# S7CAS-PLEIADES-CARTE-MERE_P01_FPGA-ALIM.net
KiCad netlist of a schematic drawn in Altium Designer
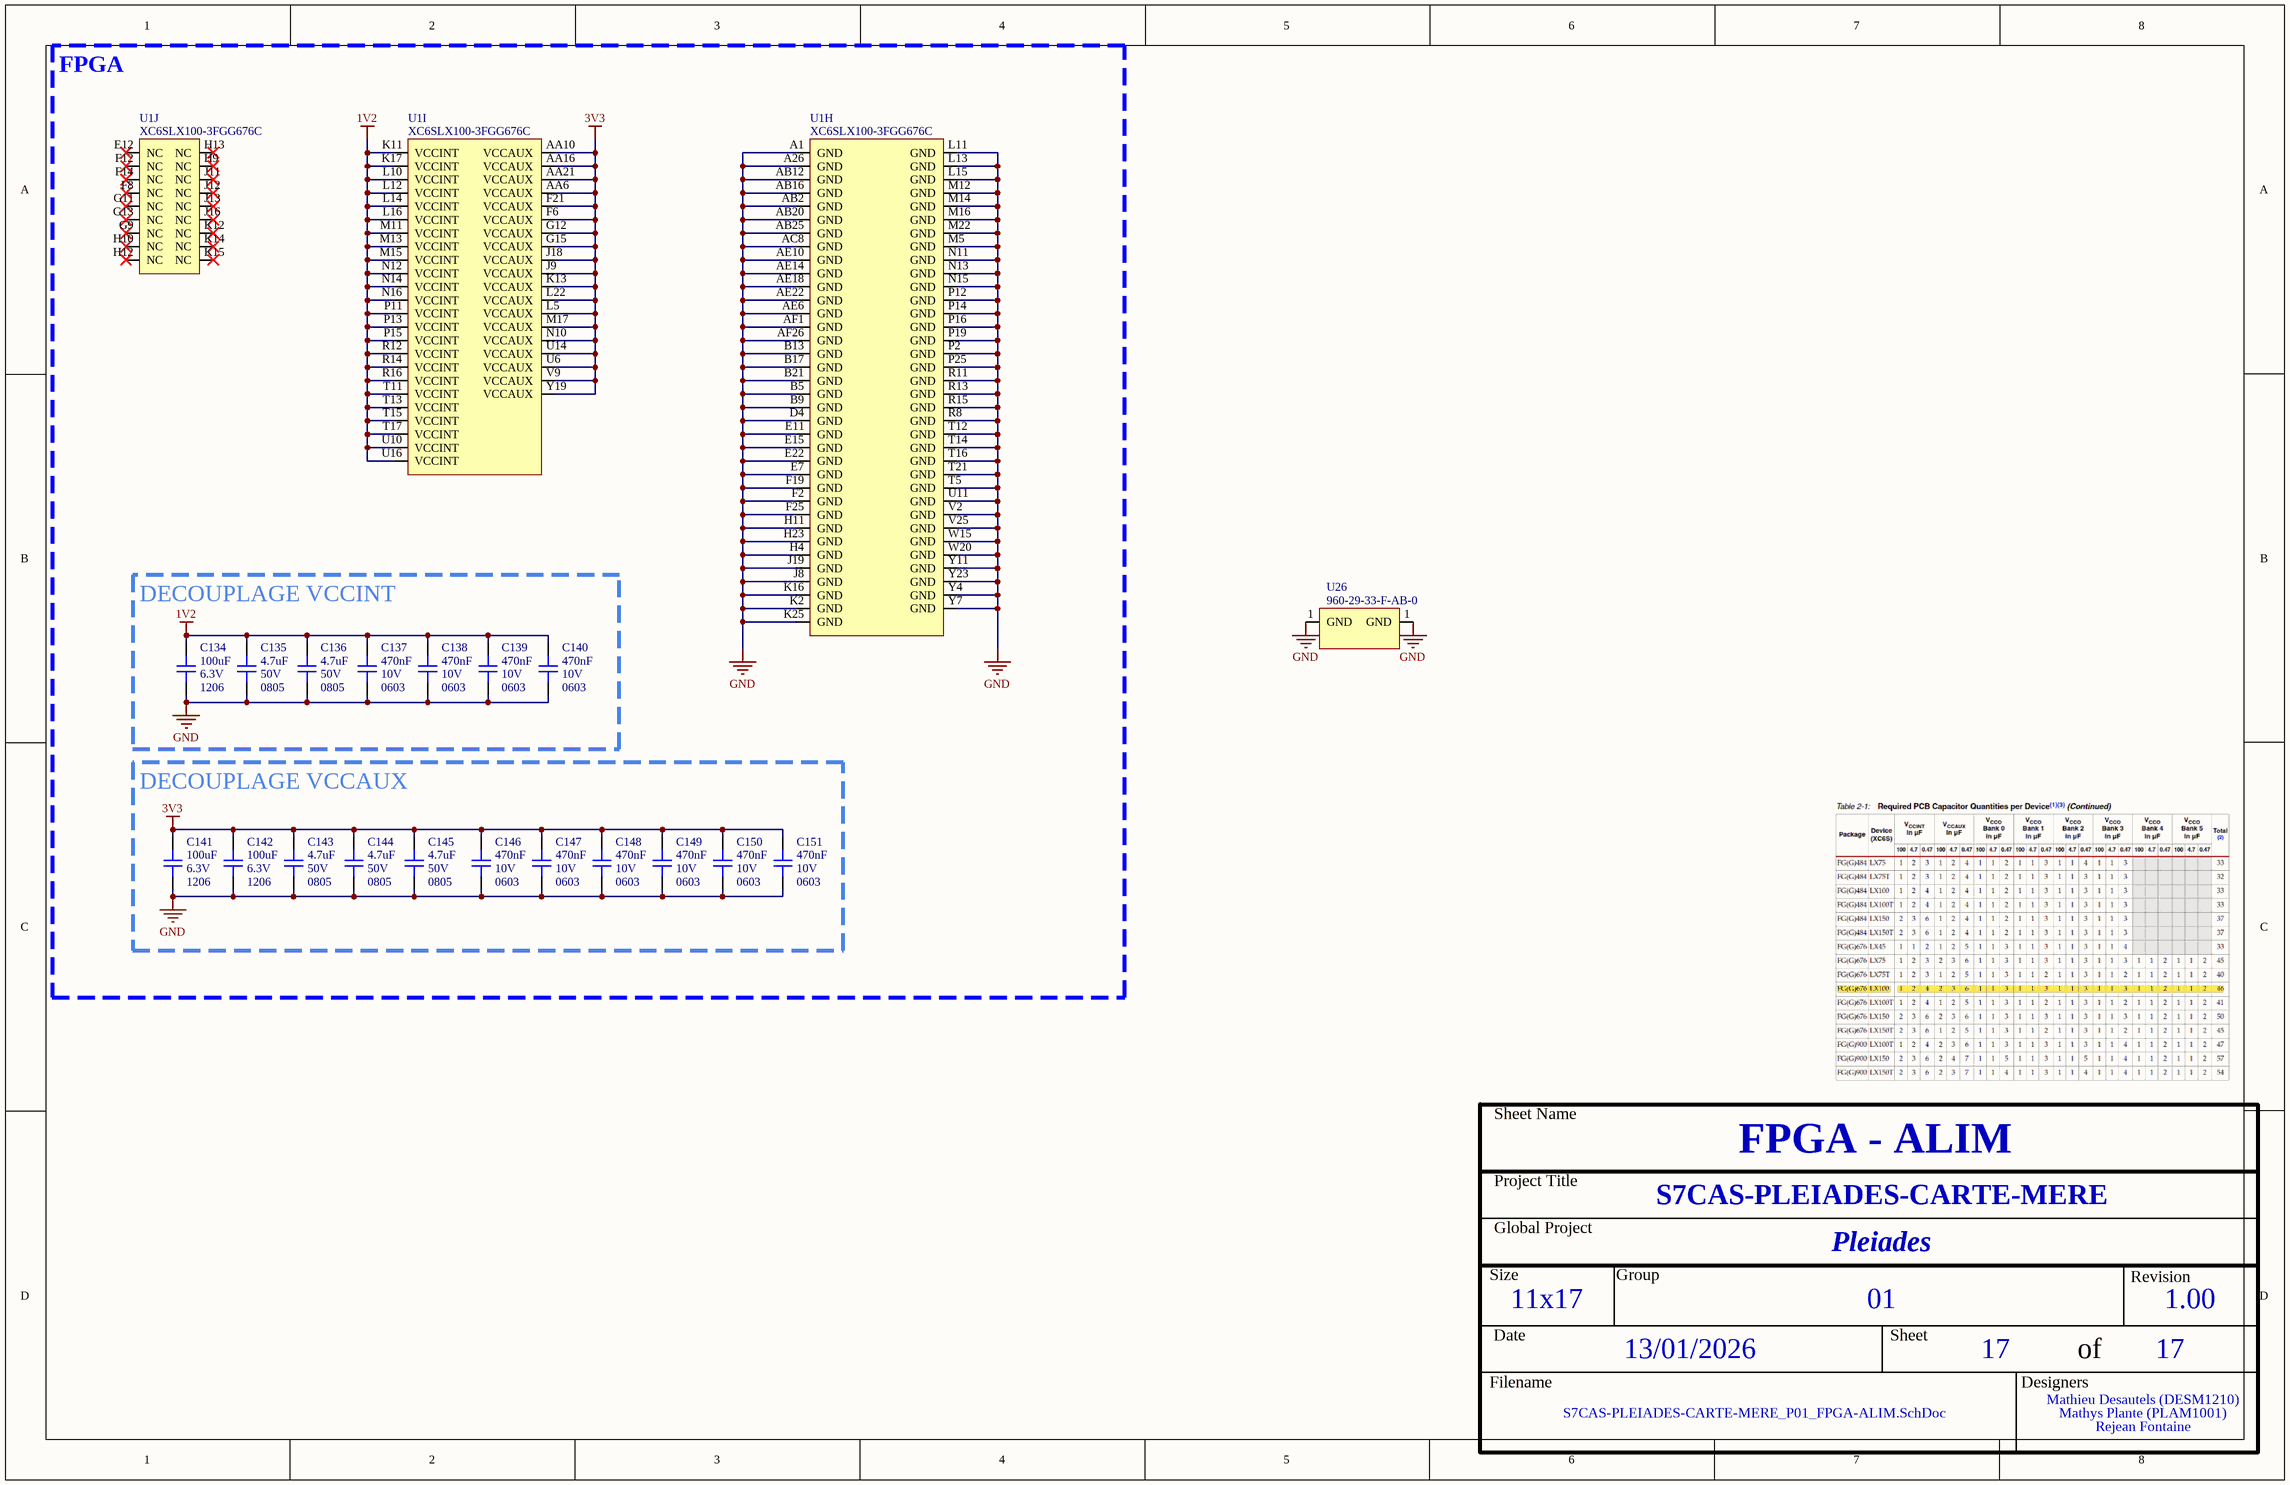
[diagram p0: S7CAS-PLEIADES-CARTE-MERE_P01_FPGA-ALIM.SchDoc]

(export (version "E")
  (design (tool "Eeschema 10.0.6"))
  (components
    (comp (ref "C134")
      (value "100uF")
      (footprint "CAP_1206")
      (description "100 µF ±20% 6.3V Ceramic Capacitor X6T 1206 (3216 Metric)")
      (fields
        (field (name "MFG") "Murata Electronics")
        (field (name "MFG PART NUMBER") "GRM31CD80J107MEA8K")
        (field (name "VOLTAGE") "6.3V")
        (field (name "PACKAGE") "1206")
        (field (name "CREATEDBY") "Jonathan Bouchard")
      )
      (libsource (lib "s7cas_lib2023") (part "CAP - 1206"))
    )
    (comp (ref "C135")
      (value "4.7uF")
      (footprint "CAP_0805")
      (description "4.7 µF ±10% 50V Ceramic Capacitor X5R 0805 (2012 Metric)")
      (fields
        (field (name "MFG") "Murata Electronics")
        (field (name "MFG PART NUMBER") "GRT21BR61H475KE13L")
        (field (name "VOLTAGE") "50V")
        (field (name "PACKAGE") "0805")
        (field (name "CREATEDBY") "Jonathan Bouchard")
      )
      (libsource (lib "s7cas_lib2023") (part "CAP - 0805"))
    )
    (comp (ref "C136")
      (value "4.7uF")
      (footprint "CAP_0805")
      (description "4.7 µF ±10% 50V Ceramic Capacitor X5R 0805 (2012 Metric)")
      (fields
        (field (name "MFG") "Murata Electronics")
        (field (name "MFG PART NUMBER") "GRT21BR61H475KE13L")
        (field (name "VOLTAGE") "50V")
        (field (name "PACKAGE") "0805")
        (field (name "CREATEDBY") "Jonathan Bouchard")
      )
      (libsource (lib "s7cas_lib2023") (part "CAP - 0805"))
    )
    (comp (ref "C137")
      (value "470nF")
      (footprint "CAP_0603")
      (description "CAP - 0603")
      (fields
        (field (name "MFG PART NUMBER") "C0603X474K8RAC")
        (field (name "VOLTAGE") "10V")
        (field (name "PACKAGE") "0603")
        (field (name "CREATEDBY") "Jonathan Bouchard")
      )
      (libsource (lib "s7cas_lib2023") (part "CAP - 0603"))
    )
    (comp (ref "C138")
      (value "470nF")
      (footprint "CAP_0603")
      (description "CAP - 0603")
      (fields
        (field (name "MFG PART NUMBER") "C0603X474K8RAC")
        (field (name "VOLTAGE") "10V")
        (field (name "PACKAGE") "0603")
        (field (name "CREATEDBY") "Jonathan Bouchard")
      )
      (libsource (lib "s7cas_lib2023") (part "CAP - 0603"))
    )
    (comp (ref "C139")
      (value "470nF")
      (footprint "CAP_0603")
      (description "CAP - 0603")
      (fields
        (field (name "MFG PART NUMBER") "C0603X474K8RAC")
        (field (name "VOLTAGE") "10V")
        (field (name "PACKAGE") "0603")
        (field (name "CREATEDBY") "Jonathan Bouchard")
      )
      (libsource (lib "s7cas_lib2023") (part "CAP - 0603"))
    )
    (comp (ref "C140")
      (value "470nF")
      (footprint "CAP_0603")
      (description "CAP - 0603")
      (fields
        (field (name "MFG PART NUMBER") "C0603X474K8RAC")
        (field (name "VOLTAGE") "10V")
        (field (name "PACKAGE") "0603")
        (field (name "CREATEDBY") "Jonathan Bouchard")
      )
      (libsource (lib "s7cas_lib2023") (part "CAP - 0603"))
    )
    (comp (ref "C141")
      (value "100uF")
      (footprint "CAP_1206")
      (description "100 µF ±20% 6.3V Ceramic Capacitor X6T 1206 (3216 Metric)")
      (fields
        (field (name "MFG") "Murata Electronics")
        (field (name "MFG PART NUMBER") "GRM31CD80J107MEA8K")
        (field (name "VOLTAGE") "6.3V")
        (field (name "PACKAGE") "1206")
        (field (name "CREATEDBY") "Jonathan Bouchard")
      )
      (libsource (lib "s7cas_lib2023") (part "CAP - 1206"))
    )
    (comp (ref "C142")
      (value "100uF")
      (footprint "CAP_1206")
      (description "100 µF ±20% 6.3V Ceramic Capacitor X6T 1206 (3216 Metric)")
      (fields
        (field (name "MFG") "Murata Electronics")
        (field (name "MFG PART NUMBER") "GRM31CD80J107MEA8K")
        (field (name "VOLTAGE") "6.3V")
        (field (name "PACKAGE") "1206")
        (field (name "CREATEDBY") "Jonathan Bouchard")
      )
      (libsource (lib "s7cas_lib2023") (part "CAP - 1206"))
    )
    (comp (ref "C143")
      (value "4.7uF")
      (footprint "CAP_0805")
      (description "4.7 µF ±10% 50V Ceramic Capacitor X5R 0805 (2012 Metric)")
      (fields
        (field (name "MFG") "Murata Electronics")
        (field (name "MFG PART NUMBER") "GRT21BR61H475KE13L")
        (field (name "VOLTAGE") "50V")
        (field (name "PACKAGE") "0805")
        (field (name "CREATEDBY") "Jonathan Bouchard")
      )
      (libsource (lib "s7cas_lib2023") (part "CAP - 0805"))
    )
    (comp (ref "C144")
      (value "4.7uF")
      (footprint "CAP_0805")
      (description "4.7 µF ±10% 50V Ceramic Capacitor X5R 0805 (2012 Metric)")
      (fields
        (field (name "MFG") "Murata Electronics")
        (field (name "MFG PART NUMBER") "GRT21BR61H475KE13L")
        (field (name "VOLTAGE") "50V")
        (field (name "PACKAGE") "0805")
        (field (name "CREATEDBY") "Jonathan Bouchard")
      )
      (libsource (lib "s7cas_lib2023") (part "CAP - 0805"))
    )
    (comp (ref "C145")
      (value "4.7uF")
      (footprint "CAP_0805")
      (description "4.7 µF ±10% 50V Ceramic Capacitor X5R 0805 (2012 Metric)")
      (fields
        (field (name "MFG") "Murata Electronics")
        (field (name "MFG PART NUMBER") "GRT21BR61H475KE13L")
        (field (name "VOLTAGE") "50V")
        (field (name "PACKAGE") "0805")
        (field (name "CREATEDBY") "Jonathan Bouchard")
      )
      (libsource (lib "s7cas_lib2023") (part "CAP - 0805"))
    )
    (comp (ref "C146")
      (value "470nF")
      (footprint "CAP_0603")
      (description "CAP - 0603")
      (fields
        (field (name "MFG PART NUMBER") "C0603X474K8RAC")
        (field (name "VOLTAGE") "10V")
        (field (name "PACKAGE") "0603")
        (field (name "CREATEDBY") "Jonathan Bouchard")
      )
      (libsource (lib "s7cas_lib2023") (part "CAP - 0603"))
    )
    (comp (ref "C147")
      (value "470nF")
      (footprint "CAP_0603")
      (description "CAP - 0603")
      (fields
        (field (name "MFG PART NUMBER") "C0603X474K8RAC")
        (field (name "VOLTAGE") "10V")
        (field (name "PACKAGE") "0603")
        (field (name "CREATEDBY") "Jonathan Bouchard")
      )
      (libsource (lib "s7cas_lib2023") (part "CAP - 0603"))
    )
    (comp (ref "C148")
      (value "470nF")
      (footprint "CAP_0603")
      (description "CAP - 0603")
      (fields
        (field (name "MFG PART NUMBER") "C0603X474K8RAC")
        (field (name "VOLTAGE") "10V")
        (field (name "PACKAGE") "0603")
        (field (name "CREATEDBY") "Jonathan Bouchard")
      )
      (libsource (lib "s7cas_lib2023") (part "CAP - 0603"))
    )
    (comp (ref "C149")
      (value "470nF")
      (footprint "CAP_0603")
      (description "CAP - 0603")
      (fields
        (field (name "MFG PART NUMBER") "C0603X474K8RAC")
        (field (name "VOLTAGE") "10V")
        (field (name "PACKAGE") "0603")
        (field (name "CREATEDBY") "Jonathan Bouchard")
      )
      (libsource (lib "s7cas_lib2023") (part "CAP - 0603"))
    )
    (comp (ref "C150")
      (value "470nF")
      (footprint "CAP_0603")
      (description "CAP - 0603")
      (fields
        (field (name "MFG PART NUMBER") "C0603X474K8RAC")
        (field (name "VOLTAGE") "10V")
        (field (name "PACKAGE") "0603")
        (field (name "CREATEDBY") "Jonathan Bouchard")
      )
      (libsource (lib "s7cas_lib2023") (part "CAP - 0603"))
    )
    (comp (ref "C151")
      (value "470nF")
      (footprint "CAP_0603")
      (description "CAP - 0603")
      (fields
        (field (name "MFG PART NUMBER") "C0603X474K8RAC")
        (field (name "VOLTAGE") "10V")
        (field (name "PACKAGE") "0603")
        (field (name "CREATEDBY") "Jonathan Bouchard")
      )
      (libsource (lib "s7cas_lib2023") (part "CAP - 0603"))
    )
    (comp (ref "U1")
      (value "XC6SLX100-3FGG676C")
      (footprint "FPGA_XILINX_FGG676")
      (description "FPGA - XILINX SPARTAN 6 480 I/O - BGA-676")
      (fields
        (field (name "VOLTAGE") "1.14 V ~ 1.26 V")
        (field (name "MFG") "Xilinx")
        (field (name "CREATEDBY") "Jonathan Bouchard")
      )
      (libsource (lib "s7cas_lib2023") (part "FPGA_XC6SLX100-3FGG676C"))
    )
    (comp (ref "U26")
      (value "960-29-33-F-AB-0")
      (footprint "3960-29-33-F-AB-0")
      (description "XXX - Description - Package")
      (libsource (lib "HeatSink_SCH") (part "960-29-33-F-AB-0"))
    )
  )
  (nets
    (net (code "1") (name "1V2") (class "Default")
      (node (ref "C134") (pin "2") (pinfunction "2_2") (pintype "passive"))
      (node (ref "C135") (pin "2") (pinfunction "2_2") (pintype "passive"))
      (node (ref "C136") (pin "2") (pinfunction "2_2") (pintype "passive"))
      (node (ref "C137") (pin "2") (pinfunction "2_2") (pintype "passive"))
      (node (ref "C138") (pin "2") (pinfunction "2_2") (pintype "passive"))
      (node (ref "C139") (pin "2") (pinfunction "2_2") (pintype "passive"))
      (node (ref "C140") (pin "2") (pinfunction "2_2") (pintype "passive"))
      (node (ref "U1") (pin "K11") (pinfunction "VCCINT_K11") (pintype "passive"))
      (node (ref "U1") (pin "K17") (pinfunction "VCCINT_K17") (pintype "passive"))
      (node (ref "U1") (pin "L10") (pinfunction "VCCINT_L10") (pintype "passive"))
      (node (ref "U1") (pin "L12") (pinfunction "VCCINT_L12") (pintype "passive"))
      (node (ref "U1") (pin "L14") (pinfunction "VCCINT_L14") (pintype "passive"))
      (node (ref "U1") (pin "L16") (pinfunction "VCCINT_L16") (pintype "passive"))
      (node (ref "U1") (pin "M11") (pinfunction "VCCINT_M11") (pintype "passive"))
      (node (ref "U1") (pin "M13") (pinfunction "VCCINT_M13") (pintype "passive"))
      (node (ref "U1") (pin "M15") (pinfunction "VCCINT_M15") (pintype "passive"))
      (node (ref "U1") (pin "N12") (pinfunction "VCCINT_N12") (pintype "passive"))
      (node (ref "U1") (pin "N14") (pinfunction "VCCINT_N14") (pintype "passive"))
      (node (ref "U1") (pin "N16") (pinfunction "VCCINT_N16") (pintype "passive"))
      (node (ref "U1") (pin "P11") (pinfunction "VCCINT_P11") (pintype "passive"))
      (node (ref "U1") (pin "P13") (pinfunction "VCCINT_P13") (pintype "passive"))
      (node (ref "U1") (pin "P15") (pinfunction "VCCINT_P15") (pintype "passive"))
      (node (ref "U1") (pin "R12") (pinfunction "VCCINT_R12") (pintype "passive"))
      (node (ref "U1") (pin "R14") (pinfunction "VCCINT_R14") (pintype "passive"))
      (node (ref "U1") (pin "R16") (pinfunction "VCCINT_R16") (pintype "passive"))
      (node (ref "U1") (pin "T11") (pinfunction "VCCINT_T11") (pintype "passive"))
      (node (ref "U1") (pin "T13") (pinfunction "VCCINT_T13") (pintype "passive"))
      (node (ref "U1") (pin "T15") (pinfunction "VCCINT_T15") (pintype "passive"))
      (node (ref "U1") (pin "T17") (pinfunction "VCCINT_T17") (pintype "passive"))
      (node (ref "U1") (pin "U10") (pinfunction "VCCINT_U10") (pintype "passive"))
      (node (ref "U1") (pin "U16") (pinfunction "VCCINT_U16") (pintype "passive"))
    )
    (net (code "2") (name "3V3") (class "Default")
      (node (ref "C141") (pin "2") (pinfunction "2_2") (pintype "passive"))
      (node (ref "C142") (pin "2") (pinfunction "2_2") (pintype "passive"))
      (node (ref "C143") (pin "2") (pinfunction "2_2") (pintype "passive"))
      (node (ref "C144") (pin "2") (pinfunction "2_2") (pintype "passive"))
      (node (ref "C145") (pin "2") (pinfunction "2_2") (pintype "passive"))
      (node (ref "C146") (pin "2") (pinfunction "2_2") (pintype "passive"))
      (node (ref "C147") (pin "2") (pinfunction "2_2") (pintype "passive"))
      (node (ref "C148") (pin "2") (pinfunction "2_2") (pintype "passive"))
      (node (ref "C149") (pin "2") (pinfunction "2_2") (pintype "passive"))
      (node (ref "C150") (pin "2") (pinfunction "2_2") (pintype "passive"))
      (node (ref "C151") (pin "2") (pinfunction "2_2") (pintype "passive"))
      (node (ref "U1") (pin "AA10") (pinfunction "VCCAUX_AA10") (pintype "passive"))
      (node (ref "U1") (pin "AA16") (pinfunction "VCCAUX_AA16") (pintype "passive"))
      (node (ref "U1") (pin "AA21") (pinfunction "VCCAUX_AA21") (pintype "passive"))
      (node (ref "U1") (pin "AA6") (pinfunction "VCCAUX_AA6") (pintype "passive"))
      (node (ref "U1") (pin "F21") (pinfunction "VCCAUX_F21") (pintype "passive"))
      (node (ref "U1") (pin "F6") (pinfunction "VCCAUX_F6") (pintype "passive"))
      (node (ref "U1") (pin "G12") (pinfunction "VCCAUX_G12") (pintype "passive"))
      (node (ref "U1") (pin "G15") (pinfunction "VCCAUX_G15") (pintype "passive"))
      (node (ref "U1") (pin "J18") (pinfunction "VCCAUX_J18") (pintype "passive"))
      (node (ref "U1") (pin "J9") (pinfunction "VCCAUX_J9") (pintype "passive"))
      (node (ref "U1") (pin "K13") (pinfunction "VCCAUX_K13") (pintype "passive"))
      (node (ref "U1") (pin "L22") (pinfunction "VCCAUX_L22") (pintype "passive"))
      (node (ref "U1") (pin "L5") (pinfunction "VCCAUX_L5") (pintype "passive"))
      (node (ref "U1") (pin "M17") (pinfunction "VCCAUX_M17") (pintype "passive"))
      (node (ref "U1") (pin "N10") (pinfunction "VCCAUX_N10") (pintype "passive"))
      (node (ref "U1") (pin "U14") (pinfunction "VCCAUX_U14") (pintype "passive"))
      (node (ref "U1") (pin "U6") (pinfunction "VCCAUX_U6") (pintype "passive"))
      (node (ref "U1") (pin "V9") (pinfunction "VCCAUX_V9") (pintype "passive"))
      (node (ref "U1") (pin "Y19") (pinfunction "VCCAUX_Y19") (pintype "passive"))
    )
    (net (code "3") (name "GND") (class "Default")
      (node (ref "C134") (pin "1") (pinfunction "1_1") (pintype "passive"))
      (node (ref "C135") (pin "1") (pinfunction "1_1") (pintype "passive"))
      (node (ref "C136") (pin "1") (pinfunction "1_1") (pintype "passive"))
      (node (ref "C137") (pin "1") (pinfunction "1_1") (pintype "passive"))
      (node (ref "C138") (pin "1") (pinfunction "1_1") (pintype "passive"))
      (node (ref "C139") (pin "1") (pinfunction "1_1") (pintype "passive"))
      (node (ref "C140") (pin "1") (pinfunction "1_1") (pintype "passive"))
      (node (ref "C141") (pin "1") (pinfunction "1_1") (pintype "passive"))
      (node (ref "C142") (pin "1") (pinfunction "1_1") (pintype "passive"))
      (node (ref "C143") (pin "1") (pinfunction "1_1") (pintype "passive"))
      (node (ref "C144") (pin "1") (pinfunction "1_1") (pintype "passive"))
      (node (ref "C145") (pin "1") (pinfunction "1_1") (pintype "passive"))
      (node (ref "C146") (pin "1") (pinfunction "1_1") (pintype "passive"))
      (node (ref "C147") (pin "1") (pinfunction "1_1") (pintype "passive"))
      (node (ref "C148") (pin "1") (pinfunction "1_1") (pintype "passive"))
      (node (ref "C149") (pin "1") (pinfunction "1_1") (pintype "passive"))
      (node (ref "C150") (pin "1") (pinfunction "1_1") (pintype "passive"))
      (node (ref "C151") (pin "1") (pinfunction "1_1") (pintype "passive"))
      (node (ref "U1") (pin "A1") (pinfunction "GND_A1") (pintype "passive"))
      (node (ref "U1") (pin "A26") (pinfunction "GND_A26") (pintype "passive"))
      (node (ref "U1") (pin "AB12") (pinfunction "GND_AB12") (pintype "passive"))
      (node (ref "U1") (pin "AB16") (pinfunction "GND_AB16") (pintype "passive"))
      (node (ref "U1") (pin "AB2") (pinfunction "GND_AB2") (pintype "passive"))
      (node (ref "U1") (pin "AB20") (pinfunction "GND_AB20") (pintype "passive"))
      (node (ref "U1") (pin "AB25") (pinfunction "GND_AB25") (pintype "passive"))
      (node (ref "U1") (pin "AC8") (pinfunction "GND_AC8") (pintype "passive"))
      (node (ref "U1") (pin "AE10") (pinfunction "GND_AE10") (pintype "passive"))
      (node (ref "U1") (pin "AE14") (pinfunction "GND_AE14") (pintype "passive"))
      (node (ref "U1") (pin "AE18") (pinfunction "GND_AE18") (pintype "passive"))
      (node (ref "U1") (pin "AE22") (pinfunction "GND_AE22") (pintype "passive"))
      (node (ref "U1") (pin "AE6") (pinfunction "GND_AE6") (pintype "passive"))
      (node (ref "U1") (pin "AF1") (pinfunction "GND_AF1") (pintype "passive"))
      (node (ref "U1") (pin "AF26") (pinfunction "GND_AF26") (pintype "passive"))
      (node (ref "U1") (pin "B13") (pinfunction "GND_B13") (pintype "passive"))
      (node (ref "U1") (pin "B17") (pinfunction "GND_B17") (pintype "passive"))
      (node (ref "U1") (pin "B21") (pinfunction "GND_B21") (pintype "passive"))
      (node (ref "U1") (pin "B5") (pinfunction "GND_B5") (pintype "passive"))
      (node (ref "U1") (pin "B9") (pinfunction "GND_B9") (pintype "passive"))
      (node (ref "U1") (pin "D4") (pinfunction "GND_D4") (pintype "passive"))
      (node (ref "U1") (pin "E11") (pinfunction "GND_E11") (pintype "passive"))
      (node (ref "U1") (pin "E15") (pinfunction "GND_E15") (pintype "passive"))
      (node (ref "U1") (pin "E22") (pinfunction "GND_E22") (pintype "passive"))
      (node (ref "U1") (pin "E7") (pinfunction "GND_E7") (pintype "passive"))
      (node (ref "U1") (pin "F19") (pinfunction "GND_F19") (pintype "passive"))
      (node (ref "U1") (pin "F2") (pinfunction "GND_F2") (pintype "passive"))
      (node (ref "U1") (pin "F25") (pinfunction "GND_F25") (pintype "passive"))
      (node (ref "U1") (pin "H11") (pinfunction "GND_H11") (pintype "passive"))
      (node (ref "U1") (pin "H23") (pinfunction "GND_H23") (pintype "passive"))
      (node (ref "U1") (pin "H4") (pinfunction "GND_H4") (pintype "passive"))
      (node (ref "U1") (pin "J19") (pinfunction "GND_J19") (pintype "passive"))
      (node (ref "U1") (pin "J8") (pinfunction "GND_J8") (pintype "passive"))
      (node (ref "U1") (pin "K16") (pinfunction "GND_K16") (pintype "passive"))
      (node (ref "U1") (pin "K2") (pinfunction "GND_K2") (pintype "passive"))
      (node (ref "U1") (pin "K25") (pinfunction "GND_K25") (pintype "passive"))
      (node (ref "U1") (pin "L11") (pinfunction "GND_L11") (pintype "passive"))
      (node (ref "U1") (pin "L13") (pinfunction "GND_L13") (pintype "passive"))
      (node (ref "U1") (pin "L15") (pinfunction "GND_L15") (pintype "passive"))
      (node (ref "U1") (pin "M12") (pinfunction "GND_M12") (pintype "passive"))
      (node (ref "U1") (pin "M14") (pinfunction "GND_M14") (pintype "passive"))
      (node (ref "U1") (pin "M16") (pinfunction "GND_M16") (pintype "passive"))
      (node (ref "U1") (pin "M22") (pinfunction "GND_M22") (pintype "passive"))
      (node (ref "U1") (pin "M5") (pinfunction "GND_M5") (pintype "passive"))
      (node (ref "U1") (pin "N11") (pinfunction "GND_N11") (pintype "passive"))
      (node (ref "U1") (pin "N13") (pinfunction "GND_N13") (pintype "passive"))
      (node (ref "U1") (pin "N15") (pinfunction "GND_N15") (pintype "passive"))
      (node (ref "U1") (pin "P12") (pinfunction "GND_P12") (pintype "passive"))
      (node (ref "U1") (pin "P14") (pinfunction "GND_P14") (pintype "passive"))
      (node (ref "U1") (pin "P16") (pinfunction "GND_P16") (pintype "passive"))
      (node (ref "U1") (pin "P19") (pinfunction "GND_P19") (pintype "passive"))
      (node (ref "U1") (pin "P2") (pinfunction "GND_P2") (pintype "passive"))
      (node (ref "U1") (pin "P25") (pinfunction "GND_P25") (pintype "passive"))
      (node (ref "U1") (pin "R11") (pinfunction "GND_R11") (pintype "passive"))
      (node (ref "U1") (pin "R13") (pinfunction "GND_R13") (pintype "passive"))
      (node (ref "U1") (pin "R15") (pinfunction "GND_R15") (pintype "passive"))
      (node (ref "U1") (pin "R8") (pinfunction "GND_R8") (pintype "passive"))
      (node (ref "U1") (pin "T12") (pinfunction "GND_T12") (pintype "passive"))
      (node (ref "U1") (pin "T14") (pinfunction "GND_T14") (pintype "passive"))
      (node (ref "U1") (pin "T16") (pinfunction "GND_T16") (pintype "passive"))
      (node (ref "U1") (pin "T21") (pinfunction "GND_T21") (pintype "passive"))
      (node (ref "U1") (pin "T5") (pinfunction "GND_T5") (pintype "passive"))
      (node (ref "U1") (pin "U11") (pinfunction "GND_U11") (pintype "passive"))
      (node (ref "U1") (pin "V2") (pinfunction "GND_V2") (pintype "passive"))
      (node (ref "U1") (pin "V25") (pinfunction "GND_V25") (pintype "passive"))
      (node (ref "U1") (pin "W15") (pinfunction "GND_W15") (pintype "passive"))
      (node (ref "U1") (pin "W20") (pinfunction "GND_W20") (pintype "passive"))
      (node (ref "U1") (pin "Y11") (pinfunction "GND_Y11") (pintype "passive"))
      (node (ref "U1") (pin "Y23") (pinfunction "GND_Y23") (pintype "passive"))
      (node (ref "U1") (pin "Y4") (pinfunction "GND_Y4") (pintype "passive"))
      (node (ref "U1") (pin "Y7") (pinfunction "GND_Y7") (pintype "passive"))
      (node (ref "U26") (pin "1") (pinfunction "GND_1") (pintype "passive"))
    )
    (net (code "4") (name "unconnected-(U1J-NC-PadE12)") (class "Default")
      (node (ref "U1") (pin "E12") (pinfunction "NC_E12") (pintype "passive+no_connect"))
    )
    (net (code "5") (name "unconnected-(U1J-NC-PadF8)") (class "Default")
      (node (ref "U1") (pin "F8") (pinfunction "NC_F8") (pintype "passive+no_connect"))
    )
    (net (code "6") (name "unconnected-(U1J-NC-PadF12)") (class "Default")
      (node (ref "U1") (pin "F12") (pinfunction "NC_F12") (pintype "passive+no_connect"))
    )
    (net (code "7") (name "unconnected-(U1J-NC-PadF14)") (class "Default")
      (node (ref "U1") (pin "F14") (pinfunction "NC_F14") (pintype "passive+no_connect"))
    )
    (net (code "8") (name "unconnected-(U1J-NC-PadG9)") (class "Default")
      (node (ref "U1") (pin "G9") (pinfunction "NC_G9") (pintype "passive+no_connect"))
    )
    (net (code "9") (name "unconnected-(U1J-NC-PadG11)") (class "Default")
      (node (ref "U1") (pin "G11") (pinfunction "NC_G11") (pintype "passive+no_connect"))
    )
    (net (code "10") (name "unconnected-(U1J-NC-PadG13)") (class "Default")
      (node (ref "U1") (pin "G13") (pinfunction "NC_G13") (pintype "passive+no_connect"))
    )
    (net (code "11") (name "unconnected-(U1J-NC-PadH9)") (class "Default")
      (node (ref "U1") (pin "H9") (pinfunction "NC_H9") (pintype "passive+no_connect"))
    )
    (net (code "12") (name "unconnected-(U1J-NC-PadH10)") (class "Default")
      (node (ref "U1") (pin "H10") (pinfunction "NC_H10") (pintype "passive+no_connect"))
    )
    (net (code "13") (name "unconnected-(U1J-NC-PadH12)") (class "Default")
      (node (ref "U1") (pin "H12") (pinfunction "NC_H12") (pintype "passive+no_connect"))
    )
    (net (code "14") (name "unconnected-(U1J-NC-PadH13)") (class "Default")
      (node (ref "U1") (pin "H13") (pinfunction "NC_H13") (pintype "passive+no_connect"))
    )
    (net (code "15") (name "unconnected-(U1J-NC-PadJ11)") (class "Default")
      (node (ref "U1") (pin "J11") (pinfunction "NC_J11") (pintype "passive+no_connect"))
    )
    (net (code "16") (name "unconnected-(U1J-NC-PadJ12)") (class "Default")
      (node (ref "U1") (pin "J12") (pinfunction "NC_J12") (pintype "passive+no_connect"))
    )
    (net (code "17") (name "unconnected-(U1J-NC-PadJ13)") (class "Default")
      (node (ref "U1") (pin "J13") (pinfunction "NC_J13") (pintype "passive+no_connect"))
    )
    (net (code "18") (name "unconnected-(U1J-NC-PadJ16)") (class "Default")
      (node (ref "U1") (pin "J16") (pinfunction "NC_J16") (pintype "passive+no_connect"))
    )
    (net (code "19") (name "unconnected-(U1J-NC-PadK12)") (class "Default")
      (node (ref "U1") (pin "K12") (pinfunction "NC_K12") (pintype "passive+no_connect"))
    )
    (net (code "20") (name "unconnected-(U1J-NC-PadK14)") (class "Default")
      (node (ref "U1") (pin "K14") (pinfunction "NC_K14") (pintype "passive+no_connect"))
    )
    (net (code "21") (name "unconnected-(U1J-NC-PadK15)") (class "Default")
      (node (ref "U1") (pin "K15") (pinfunction "NC_K15") (pintype "passive+no_connect"))
    )
  )
)
